# out.net
KiCad netlist of a schematic drawn in Altium Designer
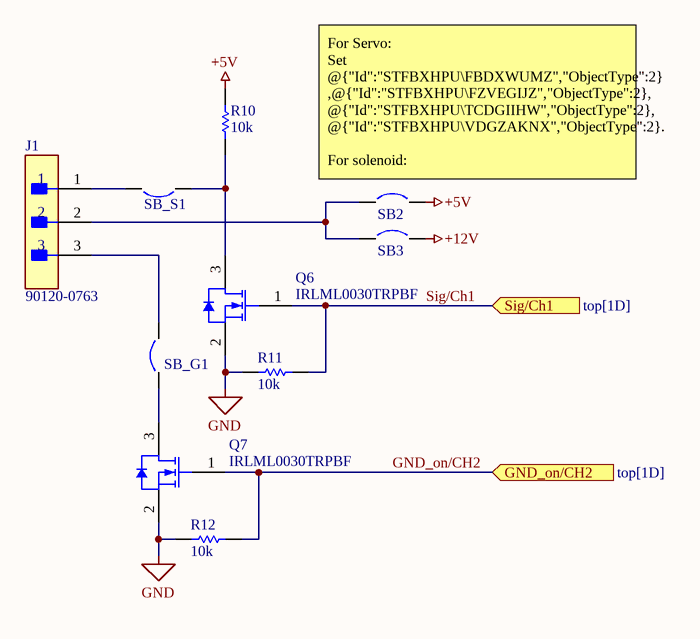
[diagram p0: out.SchDoc]

(export (version "E")
  (design (tool "Eeschema 10.0.6"))
  (components
    (comp (ref "J1")
      (value "90120-0763")
      (footprint "FP-90120-0763-MFG")
      (description "CONN HEADER VERT 3POS 2.54MM")
      (fields
        (field (name "MANUFACTURER") "Molex")
        (field (name "OCTOPART") "https://octopart.com/90120-0763-molex-655433")
      )
      (libsource (lib "Altium Content Vault") (part "0d3f023dd272f625e17a2be33dea85f"))
    )
    (comp (ref "Q6")
      (value "IRLML0030TRPBF")
      (footprint "INTR-SOT-23-3_V")
      (description "HEXFET(R) Power MOSFET, 1.3 W, 4.4 ns, -55 to 150 degC, 3-Pin SOT-23, RoHS, Tape and Reel")
      (fields (field (name "MANUFACTURER") "International Rectifier"))
      (libsource (lib "Altium Content Vault") (part "NEMOS-GSD-3"))
    )
    (comp (ref "Q7")
      (value "IRLML0030TRPBF")
      (footprint "INTR-SOT-23-3_V")
      (description "HEXFET(R) Power MOSFET, 1.3 W, 4.4 ns, -55 to 150 degC, 3-Pin SOT-23, RoHS, Tape and Reel")
      (fields (field (name "MANUFACTURER") "International Rectifier"))
      (libsource (lib "Altium Content Vault") (part "NEMOS-GSD-3"))
    )
    (comp (ref "R10")
      (value "10k")
      (footprint "RESC1609X55X30NL15T15")
      (description "Chip Resistor, 10 KOhm, +/- 1%, 0.1 W, -55 to 155 degC, 0603 (1608 Metric), RoHS, Tape and Reel")
      (fields (field (name "TOLERANCE") "1%") (field (name "MANUFACTURER") "Panasonic"))
      (libsource (lib "Altium Content Vault") (part "RES-2"))
    )
    (comp (ref "R11")
      (value "10k")
      (footprint "RESC1609X55X30NL15T15")
      (description "Chip Resistor, 10 KOhm, +/- 1%, 0.1 W, -55 to 155 degC, 0603 (1608 Metric), RoHS, Tape and Reel")
      (fields (field (name "TOLERANCE") "1%") (field (name "MANUFACTURER") "Panasonic"))
      (libsource (lib "Altium Content Vault") (part "RES-2"))
    )
    (comp (ref "R12")
      (value "10k")
      (footprint "RESC1609X55X30NL15T15")
      (description "Chip Resistor, 10 KOhm, +/- 1%, 0.1 W, -55 to 155 degC, 0603 (1608 Metric), RoHS, Tape and Reel")
      (fields (field (name "TOLERANCE") "1%") (field (name "MANUFACTURER") "Panasonic"))
      (libsource (lib "Altium Content Vault") (part "RES-2"))
    )
    (comp (ref "SB2")
      (value "~")
      (footprint "JP_SMD")
      (description "Circuit Breaker")
      (fields (field (name "PUBLISHER") "Altium Limited"))
      (libsource (lib "test_adc") (part "Circuit Breaker"))
    )
    (comp (ref "SB3")
      (value "~")
      (footprint "JP_SMD")
      (description "Circuit Breaker")
      (fields (field (name "PUBLISHER") "Altium Limited"))
      (libsource (lib "test_adc") (part "Circuit Breaker"))
    )
    (comp (ref "SB_G1")
      (value "~")
      (footprint "JP_SMD")
      (description "Circuit Breaker")
      (fields (field (name "PUBLISHER") "Altium Limited"))
      (libsource (lib "test_adc") (part "Circuit Breaker"))
    )
    (comp (ref "SB_S1")
      (value "~")
      (footprint "JP_SMD")
      (description "Circuit Breaker")
      (fields (field (name "PUBLISHER") "Altium Limited"))
      (libsource (lib "test_adc") (part "Circuit Breaker"))
    )
  )
  (nets
    (net (code "1") (name "+5V") (class "Default")
      (node (ref "R10") (pin "1") (pinfunction "1_1") (pintype "passive"))
      (node (ref "SB2") (pin "2") (pinfunction "2_2") (pintype "passive"))
    )
    (net (code "2") (name "+12V") (class "Default")
      (node (ref "SB3") (pin "2") (pinfunction "2_2") (pintype "passive"))
    )
    (net (code "3") (name "/GND_on{slash}CH2") (class "Default")
      (node (ref "Q7") (pin "1") (pinfunction "G_1") (pintype "passive"))
      (node (ref "R12") (pin "1") (pinfunction "1_1") (pintype "passive"))
    )
    (net (code "4") (name "/Sig{slash}Ch1") (class "Default")
      (node (ref "Q6") (pin "1") (pinfunction "G_1") (pintype "passive"))
      (node (ref "R11") (pin "1") (pinfunction "1_1") (pintype "passive"))
    )
    (net (code "5") (name "GND") (class "Default")
      (node (ref "Q6") (pin "2") (pinfunction "S_2") (pintype "passive"))
      (node (ref "Q7") (pin "2") (pinfunction "S_2") (pintype "passive"))
      (node (ref "R11") (pin "2") (pinfunction "2_2") (pintype "passive"))
      (node (ref "R12") (pin "2") (pinfunction "2_2") (pintype "passive"))
    )
    (net (code "6") (name "Net-(J1-Pad1)") (class "Default")
      (node (ref "J1") (pin "1") (pinfunction "1_1") (pintype "passive"))
      (node (ref "SB_S1") (pin "2") (pinfunction "2_2") (pintype "passive"))
    )
    (net (code "7") (name "Net-(J1-Pad2)") (class "Default")
      (node (ref "J1") (pin "2") (pinfunction "2_2") (pintype "passive"))
      (node (ref "SB2") (pin "1") (pinfunction "1_1") (pintype "passive"))
      (node (ref "SB3") (pin "1") (pinfunction "1_1") (pintype "passive"))
    )
    (net (code "8") (name "Net-(J1-Pad3)") (class "Default")
      (node (ref "J1") (pin "3") (pinfunction "3_3") (pintype "passive"))
      (node (ref "SB_G1") (pin "2") (pinfunction "2_2") (pintype "passive"))
    )
    (net (code "9") (name "Net-(Q6-D)") (class "Default")
      (node (ref "Q6") (pin "3") (pinfunction "D_3") (pintype "passive"))
      (node (ref "R10") (pin "2") (pinfunction "2_2") (pintype "passive"))
      (node (ref "SB_S1") (pin "1") (pinfunction "1_1") (pintype "passive"))
    )
    (net (code "10") (name "Net-(Q7-D)") (class "Default")
      (node (ref "Q7") (pin "3") (pinfunction "D_3") (pintype "passive"))
      (node (ref "SB_G1") (pin "1") (pinfunction "1_1") (pintype "passive"))
    )
  )
)
